# Phiips_212_r3.net
KiCad netlist of a schematic drawn in EAGLE
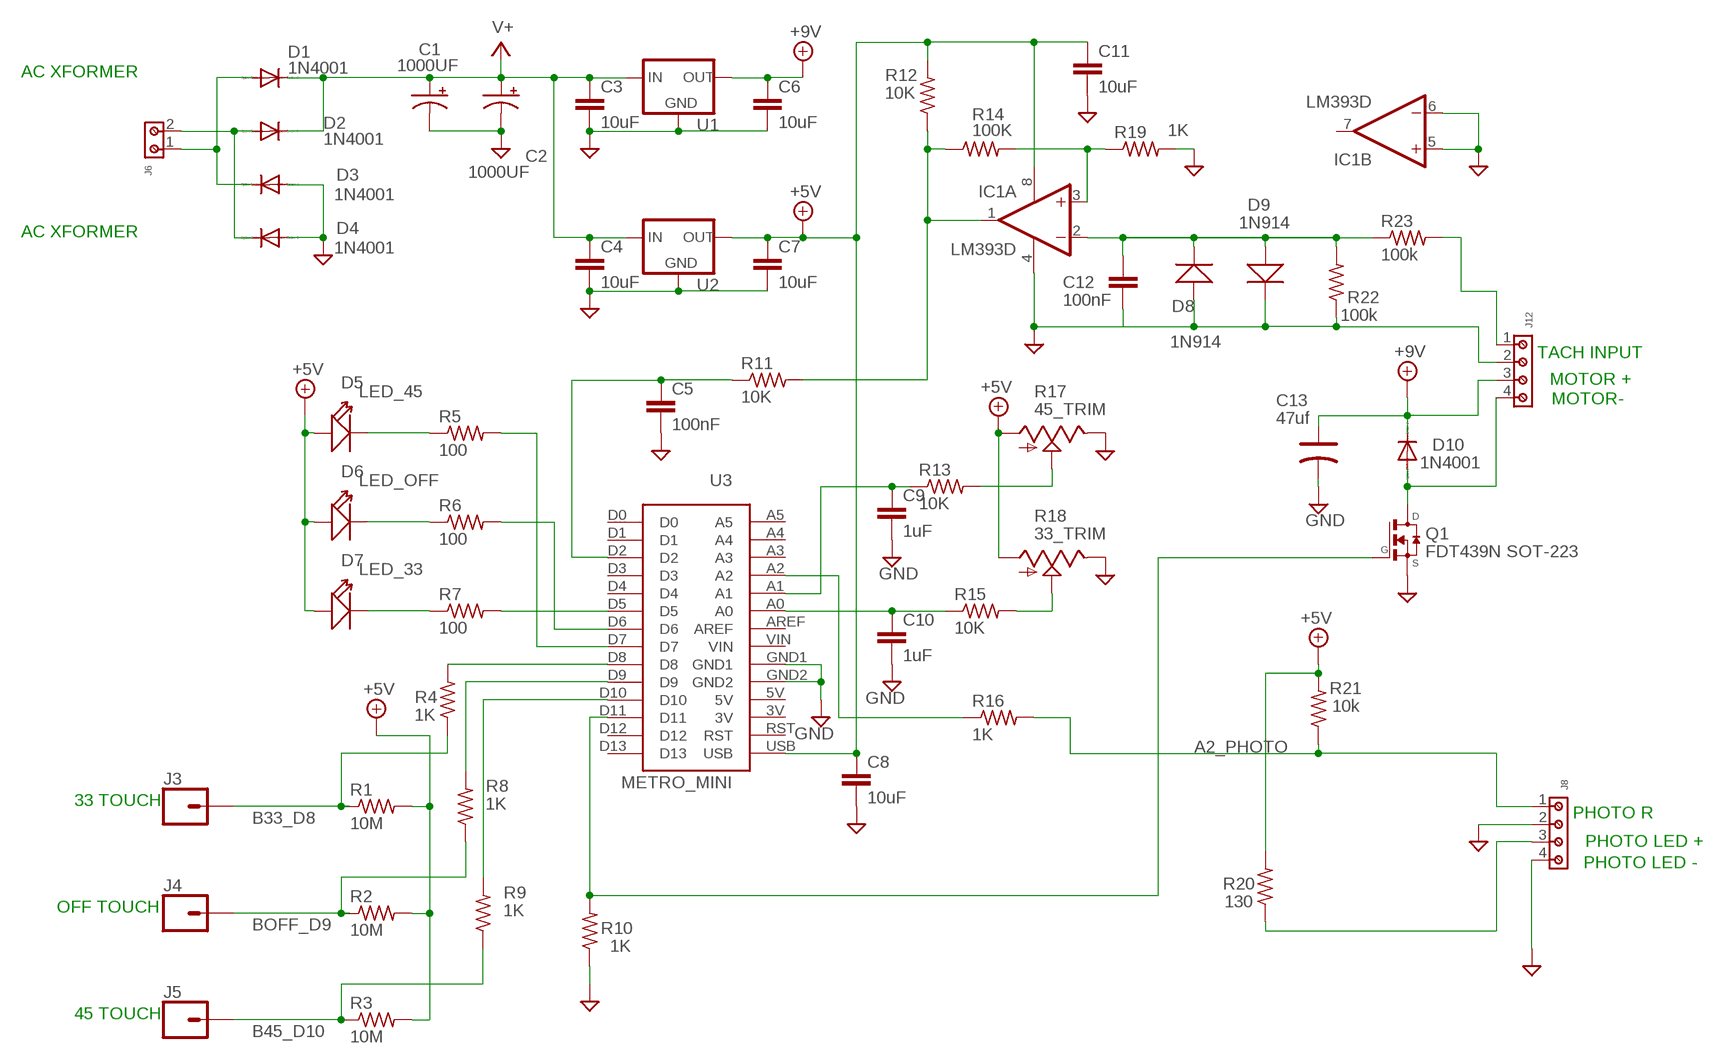
[diagram p0: schematic, sheet 1]

(export (version "E")
  (design (tool "Eeschema 10.0.6"))
  (components
    (comp (ref "C1")
      (value "1000UF")
      (footprint "eagle-import:CAPPAD1700W60L1040D500P")
      (libsource (lib "eagle-import") (part "1000UF"))
    )
    (comp (ref "C2")
      (value "1000UF")
      (footprint "eagle-import:CAPPAD1700W60L1040D500P")
      (libsource (lib "eagle-import") (part "1000UF"))
    )
    (comp (ref "C3")
      (value "10uF")
      (footprint "eagle-import:1206")
      (libsource (lib "eagle-import") (part "10UF-1206-6.3V-20%"))
    )
    (comp (ref "C4")
      (value "10uF")
      (footprint "eagle-import:1206")
      (libsource (lib "eagle-import") (part "10UF-1206-6.3V-20%"))
    )
    (comp (ref "C5")
      (value "100nF")
      (footprint "eagle-import:0805")
      (libsource (lib "eagle-import") (part "10UF-0805-10V-10%"))
    )
    (comp (ref "C6")
      (value "10uF")
      (footprint "eagle-import:1206")
      (libsource (lib "eagle-import") (part "10UF-1206-6.3V-20%"))
    )
    (comp (ref "C7")
      (value "10uF")
      (footprint "eagle-import:1206")
      (libsource (lib "eagle-import") (part "10UF-1206-6.3V-20%"))
    )
    (comp (ref "C8")
      (value "10uF")
      (footprint "eagle-import:1206")
      (libsource (lib "eagle-import") (part "10UF-1206-6.3V-20%"))
    )
    (comp (ref "C9")
      (value "1uF")
      (footprint "eagle-import:1206")
      (libsource (lib "eagle-import") (part "10UF-1206-6.3V-20%"))
    )
    (comp (ref "C10")
      (value "1uF")
      (footprint "eagle-import:1206")
      (libsource (lib "eagle-import") (part "10UF-1206-6.3V-20%"))
    )
    (comp (ref "C11")
      (value "10uF")
      (footprint "eagle-import:1206")
      (libsource (lib "eagle-import") (part "10UF-1206-6.3V-20%"))
    )
    (comp (ref "C12")
      (value "100nF")
      (footprint "eagle-import:0805")
      (libsource (lib "eagle-import") (part "10UF-0805-10V-10%"))
    )
    (comp (ref "C13")
      (value "47uf")
      (footprint "eagle-import:AVX-D")
      (fields (field (name "MPN") "TAJD477*006#NJ"))
      (libsource (lib "eagle-import") (part "TANTALUM-SMD-470UF-6.3V(AVX-D)"))
    )
    (comp (ref "D1")
      (value "1N4001")
      (footprint "eagle-import:DO41-10")
      (libsource (lib "eagle-import") (part "1N4004"))
    )
    (comp (ref "D2")
      (value "1N4001")
      (footprint "eagle-import:DO41-10")
      (libsource (lib "eagle-import") (part "1N4004"))
    )
    (comp (ref "D3")
      (value "1N4001")
      (footprint "eagle-import:DO41-10")
      (libsource (lib "eagle-import") (part "1N4004"))
    )
    (comp (ref "D4")
      (value "1N4001")
      (footprint "eagle-import:DO41-10")
      (libsource (lib "eagle-import") (part "1N4004"))
    )
    (comp (ref "D5")
      (value "LED_45")
      (footprint "eagle-import:LED2-2.54-D5.0MM")
      (fields (field (name "MPN") "504WC"))
      (libsource (lib "eagle-import") (part "DIP-LED-TRANSPARENT-WHITE(2P-D5MM)"))
    )
    (comp (ref "D6")
      (value "LED_OFF")
      (footprint "eagle-import:LED2-2.54-D5.0MM")
      (fields (field (name "MPN") "504WC"))
      (libsource (lib "eagle-import") (part "DIP-LED-TRANSPARENT-WHITE(2P-D5MM)"))
    )
    (comp (ref "D7")
      (value "LED_33")
      (footprint "eagle-import:LED2-2.54-D5.0MM")
      (fields (field (name "MPN") "504WC"))
      (libsource (lib "eagle-import") (part "DIP-LED-TRANSPARENT-WHITE(2P-D5MM)"))
    )
    (comp (ref "D8")
      (value "1N914")
      (footprint "eagle-import:DO-41")
      (fields (field (name "MPN") "1N4004"))
      (libsource (lib "eagle-import") (part "DIP-DIODE-400V-1A(DO-41)"))
    )
    (comp (ref "D9")
      (value "1N914")
      (footprint "eagle-import:DO-41")
      (fields (field (name "MPN") "1N4004"))
      (libsource (lib "eagle-import") (part "DIP-DIODE-400V-1A(DO-41)"))
    )
    (comp (ref "D10")
      (value "1N4001")
      (footprint "eagle-import:DO41-10")
      (libsource (lib "eagle-import") (part "1N4004"))
    )
    (comp (ref "IC1")
      (value "LM393D")
      (footprint "eagle-import:SO08")
      (libsource (lib "eagle-import") (part "LM393D"))
    )
    (comp (ref "J3")
      (value "CONN_01OFFSET")
      (footprint "eagle-import:1X01_OFFSET")
      (libsource (lib "eagle-import") (part "CONN_01OFFSET"))
    )
    (comp (ref "J4")
      (value "CONN_01OFFSET")
      (footprint "eagle-import:1X01_OFFSET")
      (libsource (lib "eagle-import") (part "CONN_01OFFSET"))
    )
    (comp (ref "J5")
      (value "CONN_01OFFSET")
      (footprint "eagle-import:1X01_OFFSET")
      (libsource (lib "eagle-import") (part "CONN_01OFFSET"))
    )
    (comp (ref "J6")
      (value "691131710002")
      (footprint "eagle-import:691131710002")
      (libsource (lib "eagle-import") (part "691131710002"))
    )
    (comp (ref "J8")
      (value "691131710004")
      (footprint "eagle-import:691131710004")
      (libsource (lib "eagle-import") (part "691131710004"))
    )
    (comp (ref "J12")
      (value "691131710004")
      (footprint "eagle-import:691131710004")
      (libsource (lib "eagle-import") (part "691131710004"))
    )
    (comp (ref "Q1")
      (value "FDT439N SOT-223")
      (footprint "eagle-import:SOT-223")
      (libsource (lib "eagle-import") (part "FDT439NSOT-223"))
    )
    (comp (ref "R1")
      (value "10M")
      (footprint "eagle-import:M1206")
      (libsource (lib "eagle-import") (part "R-US_M1206"))
    )
    (comp (ref "R2")
      (value "10M")
      (footprint "eagle-import:M1206")
      (libsource (lib "eagle-import") (part "R-US_M1206"))
    )
    (comp (ref "R3")
      (value "10M")
      (footprint "eagle-import:M1206")
      (libsource (lib "eagle-import") (part "R-US_M1206"))
    )
    (comp (ref "R4")
      (value "1K")
      (footprint "eagle-import:M1206")
      (libsource (lib "eagle-import") (part "R-US_M1206"))
    )
    (comp (ref "R5")
      (value "100")
      (footprint "eagle-import:M1206")
      (libsource (lib "eagle-import") (part "R-US_M1206"))
    )
    (comp (ref "R6")
      (value "100")
      (footprint "eagle-import:M1206")
      (libsource (lib "eagle-import") (part "R-US_M1206"))
    )
    (comp (ref "R7")
      (value "100")
      (footprint "eagle-import:M1206")
      (libsource (lib "eagle-import") (part "R-US_M1206"))
    )
    (comp (ref "R8")
      (value "1K")
      (footprint "eagle-import:M1206")
      (libsource (lib "eagle-import") (part "R-US_M1206"))
    )
    (comp (ref "R9")
      (value "1K")
      (footprint "eagle-import:M1206")
      (libsource (lib "eagle-import") (part "R-US_M1206"))
    )
    (comp (ref "R10")
      (value "1K")
      (footprint "eagle-import:M1206")
      (libsource (lib "eagle-import") (part "R-US_M1206"))
    )
    (comp (ref "R11")
      (value "10K")
      (footprint "eagle-import:M1206")
      (libsource (lib "eagle-import") (part "R-US_M1206"))
    )
    (comp (ref "R12")
      (value "10K")
      (footprint "eagle-import:M1206")
      (libsource (lib "eagle-import") (part "R-US_M1206"))
    )
    (comp (ref "R13")
      (value "10K")
      (footprint "eagle-import:M1206")
      (libsource (lib "eagle-import") (part "R-US_M1206"))
    )
    (comp (ref "R14")
      (value "100K")
      (footprint "eagle-import:M1206")
      (libsource (lib "eagle-import") (part "R-US_M1206"))
    )
    (comp (ref "R15")
      (value "10K")
      (footprint "eagle-import:M1206")
      (libsource (lib "eagle-import") (part "R-US_M1206"))
    )
    (comp (ref "R16")
      (value "1K")
      (footprint "eagle-import:M1206")
      (libsource (lib "eagle-import") (part "R-US_M1206"))
    )
    (comp (ref "R17")
      (value "45_TRIM")
      (footprint "eagle-import:PH212_POT")
      (libsource (lib "eagle-import") (part "POTS212_POT"))
    )
    (comp (ref "R18")
      (value "33_TRIM")
      (footprint "eagle-import:PH212_POT")
      (libsource (lib "eagle-import") (part "POTS212_POT"))
    )
    (comp (ref "R19")
      (value "1K")
      (footprint "eagle-import:M1206")
      (libsource (lib "eagle-import") (part "R-US_M1206"))
    )
    (comp (ref "R20")
      (value "130")
      (footprint "eagle-import:M1206")
      (libsource (lib "eagle-import") (part "R-US_M1206"))
    )
    (comp (ref "R21")
      (value "10k")
      (footprint "eagle-import:M1206")
      (libsource (lib "eagle-import") (part "R-US_M1206"))
    )
    (comp (ref "R22")
      (value "100k")
      (footprint "eagle-import:M1206")
      (libsource (lib "eagle-import") (part "R-US_M1206"))
    )
    (comp (ref "R23")
      (value "100k")
      (footprint "eagle-import:M1206")
      (libsource (lib "eagle-import") (part "R-US_M1206"))
    )
    (comp (ref "U1")
      (value "V_REG_78XXSIDE")
      (footprint "eagle-import:78XXL")
      (libsource (lib "eagle-import") (part "V_REG_78XXSIDE"))
    )
    (comp (ref "U2")
      (value "V_REG_78XXSIDE")
      (footprint "eagle-import:78XXL")
      (libsource (lib "eagle-import") (part "V_REG_78XXSIDE"))
    )
    (comp (ref "U3")
      (value "METRO_MINI")
      (footprint "eagle-import:METRO_MINI")
      (libsource (lib "eagle-import") (part "METRO_MINI"))
    )
  )
  (nets
    (net (code "1") (name "+5V") (class "Default")
      (node (ref "C11") (pin "1") (pinfunction "1_1") (pintype "passive"))
      (node (ref "C7") (pin "1") (pinfunction "1_1") (pintype "passive"))
      (node (ref "C8") (pin "1") (pinfunction "1_1") (pintype "passive"))
      (node (ref "D5") (pin "+") (pinfunction "+_+") (pintype "passive"))
      (node (ref "D6") (pin "+") (pinfunction "+_+") (pintype "passive"))
      (node (ref "D7") (pin "+") (pinfunction "+_+") (pintype "passive"))
      (node (ref "IC1") (pin "8") (pinfunction "V+_8") (pintype "power_in"))
      (node (ref "R1") (pin "2") (pinfunction "2_2") (pintype "passive"))
      (node (ref "R12") (pin "2") (pinfunction "2_2") (pintype "passive"))
      (node (ref "R17") (pin "1") (pinfunction "A_1") (pintype "passive"))
      (node (ref "R18") (pin "1") (pinfunction "A_1") (pintype "passive"))
      (node (ref "R2") (pin "2") (pinfunction "2_2") (pintype "passive"))
      (node (ref "R20") (pin "2") (pinfunction "2_2") (pintype "passive"))
      (node (ref "R21") (pin "2") (pinfunction "2_2") (pintype "passive"))
      (node (ref "R3") (pin "2") (pinfunction "2_2") (pintype "passive"))
      (node (ref "U2") (pin "OUT") (pinfunction "OUT_OUT") (pintype "passive"))
      (node (ref "U3") (pin "USB") (pinfunction "USB_USB") (pintype "power_in"))
    )
    (net (code "2") (name "+9V") (class "Default")
      (node (ref "C13") (pin "+") (pinfunction "+_+") (pintype "passive"))
      (node (ref "C6") (pin "1") (pinfunction "1_1") (pintype "passive"))
      (node (ref "D10") (pin "C") (pinfunction "C_C") (pintype "passive"))
      (node (ref "J12") (pin "3") (pinfunction "3_3") (pintype "passive"))
      (node (ref "U1") (pin "OUT") (pinfunction "OUT_OUT") (pintype "passive"))
    )
    (net (code "3") (name "/A2_PHOTO") (class "Default")
      (node (ref "J8") (pin "1") (pinfunction "1_1") (pintype "passive"))
      (node (ref "R16") (pin "2") (pinfunction "2_2") (pintype "passive"))
      (node (ref "R21") (pin "1") (pinfunction "1_1") (pintype "passive"))
    )
    (net (code "4") (name "/B33_D8") (class "Default")
      (node (ref "J3") (pin "1") (pinfunction "1_1") (pintype "passive"))
      (node (ref "R1") (pin "1") (pinfunction "1_1") (pintype "passive"))
      (node (ref "R4") (pin "1") (pinfunction "1_1") (pintype "passive"))
    )
    (net (code "5") (name "/B45_D10") (class "Default")
      (node (ref "J5") (pin "1") (pinfunction "1_1") (pintype "passive"))
      (node (ref "R3") (pin "1") (pinfunction "1_1") (pintype "passive"))
      (node (ref "R9") (pin "1") (pinfunction "1_1") (pintype "passive"))
    )
    (net (code "6") (name "/BOFF_D9") (class "Default")
      (node (ref "J4") (pin "1") (pinfunction "1_1") (pintype "passive"))
      (node (ref "R2") (pin "1") (pinfunction "1_1") (pintype "passive"))
      (node (ref "R8") (pin "1") (pinfunction "1_1") (pintype "passive"))
    )
    (net (code "7") (name "GND") (class "Default")
      (node (ref "C1") (pin "2") (pinfunction "-_2") (pintype "passive"))
      (node (ref "C10") (pin "2") (pinfunction "2_2") (pintype "passive"))
      (node (ref "C11") (pin "2") (pinfunction "2_2") (pintype "passive"))
      (node (ref "C12") (pin "2") (pinfunction "2_2") (pintype "passive"))
      (node (ref "C13") (pin "-") (pinfunction "-_-") (pintype "passive"))
      (node (ref "C2") (pin "2") (pinfunction "-_2") (pintype "passive"))
      (node (ref "C3") (pin "2") (pinfunction "2_2") (pintype "passive"))
      (node (ref "C4") (pin "2") (pinfunction "2_2") (pintype "passive"))
      (node (ref "C5") (pin "2") (pinfunction "2_2") (pintype "passive"))
      (node (ref "C6") (pin "2") (pinfunction "2_2") (pintype "passive"))
      (node (ref "C7") (pin "2") (pinfunction "2_2") (pintype "passive"))
      (node (ref "C8") (pin "2") (pinfunction "2_2") (pintype "passive"))
      (node (ref "C9") (pin "2") (pinfunction "2_2") (pintype "passive"))
      (node (ref "D3") (pin "A") (pinfunction "A_A") (pintype "passive"))
      (node (ref "D4") (pin "A") (pinfunction "A_A") (pintype "passive"))
      (node (ref "D8") (pin "1") (pinfunction "+_1") (pintype "passive"))
      (node (ref "D9") (pin "2") (pinfunction "-_2") (pintype "passive"))
      (node (ref "IC1") (pin "4") (pinfunction "V-_4") (pintype "power_in"))
      (node (ref "IC1") (pin "5") (pinfunction "+IN_5") (pintype "input"))
      (node (ref "IC1") (pin "6") (pinfunction "-IN_6") (pintype "input"))
      (node (ref "J12") (pin "2") (pinfunction "2_2") (pintype "passive"))
      (node (ref "J8") (pin "2") (pinfunction "2_2") (pintype "passive"))
      (node (ref "J8") (pin "4") (pinfunction "4_4") (pintype "passive"))
      (node (ref "Q1") (pin "3") (pinfunction "S_3") (pintype "passive"))
      (node (ref "R10") (pin "1") (pinfunction "1_1") (pintype "passive"))
      (node (ref "R17") (pin "3") (pinfunction "E_3") (pintype "passive"))
      (node (ref "R18") (pin "3") (pinfunction "E_3") (pintype "passive"))
      (node (ref "R19") (pin "2") (pinfunction "2_2") (pintype "passive"))
      (node (ref "R22") (pin "1") (pinfunction "1_1") (pintype "passive"))
      (node (ref "U1") (pin "GND") (pinfunction "GND_GND") (pintype "input"))
      (node (ref "U2") (pin "GND") (pinfunction "GND_GND") (pintype "input"))
      (node (ref "U3") (pin "GND1") (pinfunction "GND1_GND1") (pintype "power_in"))
      (node (ref "U3") (pin "GND2") (pinfunction "GND2_GND2") (pintype "power_in"))
    )
    (net (code "8") (name "Net-(C5-Pad1)") (class "Default")
      (node (ref "C5") (pin "1") (pinfunction "1_1") (pintype "passive"))
      (node (ref "R11") (pin "1") (pinfunction "1_1") (pintype "passive"))
      (node (ref "U3") (pin "D2") (pinfunction "D2_D2") (pintype "bidirectional"))
    )
    (net (code "9") (name "Net-(C9-Pad1)") (class "Default")
      (node (ref "C9") (pin "1") (pinfunction "1_1") (pintype "passive"))
      (node (ref "R13") (pin "1") (pinfunction "1_1") (pintype "passive"))
      (node (ref "U3") (pin "A1") (pinfunction "A1_A1") (pintype "bidirectional"))
    )
    (net (code "10") (name "Net-(C10-Pad1)") (class "Default")
      (node (ref "C10") (pin "1") (pinfunction "1_1") (pintype "passive"))
      (node (ref "R15") (pin "1") (pinfunction "1_1") (pintype "passive"))
      (node (ref "U3") (pin "A0") (pinfunction "A0_A0") (pintype "bidirectional"))
    )
    (net (code "11") (name "Net-(D1-PadA)") (class "Default")
      (node (ref "D1") (pin "A") (pinfunction "A_A") (pintype "passive"))
      (node (ref "D3") (pin "C") (pinfunction "C_C") (pintype "passive"))
      (node (ref "J6") (pin "1") (pinfunction "1_1") (pintype "passive"))
    )
    (net (code "12") (name "Net-(D2-PadA)") (class "Default")
      (node (ref "D2") (pin "A") (pinfunction "A_A") (pintype "passive"))
      (node (ref "D4") (pin "C") (pinfunction "C_C") (pintype "passive"))
      (node (ref "J6") (pin "2") (pinfunction "2_2") (pintype "passive"))
    )
    (net (code "13") (name "Net-(D5-Pad-)") (class "Default")
      (node (ref "D5") (pin "-") (pinfunction "-_-") (pintype "passive"))
      (node (ref "R5") (pin "1") (pinfunction "1_1") (pintype "passive"))
    )
    (net (code "14") (name "Net-(D6-Pad-)") (class "Default")
      (node (ref "D6") (pin "-") (pinfunction "-_-") (pintype "passive"))
      (node (ref "R6") (pin "1") (pinfunction "1_1") (pintype "passive"))
    )
    (net (code "15") (name "Net-(D7-Pad-)") (class "Default")
      (node (ref "D7") (pin "-") (pinfunction "-_-") (pintype "passive"))
      (node (ref "R7") (pin "1") (pinfunction "1_1") (pintype "passive"))
    )
    (net (code "16") (name "Net-(D8--)") (class "Default")
      (node (ref "C12") (pin "1") (pinfunction "1_1") (pintype "passive"))
      (node (ref "D8") (pin "2") (pinfunction "-_2") (pintype "passive"))
      (node (ref "D9") (pin "1") (pinfunction "+_1") (pintype "passive"))
      (node (ref "IC1") (pin "2") (pinfunction "-IN_2") (pintype "input"))
      (node (ref "R22") (pin "2") (pinfunction "2_2") (pintype "passive"))
      (node (ref "R23") (pin "1") (pinfunction "1_1") (pintype "passive"))
    )
    (net (code "17") (name "Net-(D10-PadA)") (class "Default")
      (node (ref "D10") (pin "A") (pinfunction "A_A") (pintype "passive"))
      (node (ref "J12") (pin "4") (pinfunction "4_4") (pintype "passive"))
      (node (ref "Q1") (pin "2") (pinfunction "D_2") (pintype "passive"))
      (node (ref "Q1") (pin "4") (pinfunction "D_4") (pintype "passive"))
    )
    (net (code "18") (name "Net-(IC1A-+IN)") (class "Default")
      (node (ref "IC1") (pin "3") (pinfunction "+IN_3") (pintype "input"))
      (node (ref "R14") (pin "2") (pinfunction "2_2") (pintype "passive"))
      (node (ref "R19") (pin "1") (pinfunction "1_1") (pintype "passive"))
    )
    (net (code "19") (name "Net-(IC1A-OUT)") (class "Default")
      (node (ref "IC1") (pin "1") (pinfunction "OUT_1") (pintype "output"))
      (node (ref "R11") (pin "2") (pinfunction "2_2") (pintype "passive"))
      (node (ref "R12") (pin "1") (pinfunction "1_1") (pintype "passive"))
      (node (ref "R14") (pin "1") (pinfunction "1_1") (pintype "passive"))
    )
    (net (code "20") (name "Net-(J8-Pad3)") (class "Default")
      (node (ref "J8") (pin "3") (pinfunction "3_3") (pintype "passive"))
      (node (ref "R20") (pin "1") (pinfunction "1_1") (pintype "passive"))
    )
    (net (code "21") (name "Net-(J12-Pad1)") (class "Default")
      (node (ref "J12") (pin "1") (pinfunction "1_1") (pintype "passive"))
      (node (ref "R23") (pin "2") (pinfunction "2_2") (pintype "passive"))
    )
    (net (code "22") (name "Net-(Q1-G)") (class "Default")
      (node (ref "Q1") (pin "1") (pinfunction "G_1") (pintype "passive"))
      (node (ref "R10") (pin "2") (pinfunction "2_2") (pintype "passive"))
      (node (ref "U3") (pin "D11") (pinfunction "D11_D11") (pintype "bidirectional"))
    )
    (net (code "23") (name "Net-(R4-Pad2)") (class "Default")
      (node (ref "R4") (pin "2") (pinfunction "2_2") (pintype "passive"))
      (node (ref "U3") (pin "D8") (pinfunction "D8_D8") (pintype "bidirectional"))
    )
    (net (code "24") (name "Net-(R5-Pad2)") (class "Default")
      (node (ref "R5") (pin "2") (pinfunction "2_2") (pintype "passive"))
      (node (ref "U3") (pin "D7") (pinfunction "D7_D7") (pintype "bidirectional"))
    )
    (net (code "25") (name "Net-(R6-Pad2)") (class "Default")
      (node (ref "R6") (pin "2") (pinfunction "2_2") (pintype "passive"))
      (node (ref "U3") (pin "D6") (pinfunction "D6_D6") (pintype "bidirectional"))
    )
    (net (code "26") (name "Net-(R7-Pad2)") (class "Default")
      (node (ref "R7") (pin "2") (pinfunction "2_2") (pintype "passive"))
      (node (ref "U3") (pin "D5") (pinfunction "D5_D5") (pintype "bidirectional"))
    )
    (net (code "27") (name "Net-(R8-Pad2)") (class "Default")
      (node (ref "R8") (pin "2") (pinfunction "2_2") (pintype "passive"))
      (node (ref "U3") (pin "D9") (pinfunction "D9_D9") (pintype "bidirectional"))
    )
    (net (code "28") (name "Net-(R9-Pad2)") (class "Default")
      (node (ref "R9") (pin "2") (pinfunction "2_2") (pintype "passive"))
      (node (ref "U3") (pin "D10") (pinfunction "D10_D10") (pintype "bidirectional"))
    )
    (net (code "29") (name "Net-(R16-Pad1)") (class "Default")
      (node (ref "R16") (pin "1") (pinfunction "1_1") (pintype "passive"))
      (node (ref "U3") (pin "A2") (pinfunction "A2_A2") (pintype "bidirectional"))
    )
    (net (code "30") (name "Net-(R17-S)") (class "Default")
      (node (ref "R13") (pin "2") (pinfunction "2_2") (pintype "passive"))
      (node (ref "R17") (pin "2") (pinfunction "S_2") (pintype "passive"))
    )
    (net (code "31") (name "Net-(R18-S)") (class "Default")
      (node (ref "R15") (pin "2") (pinfunction "2_2") (pintype "passive"))
      (node (ref "R18") (pin "2") (pinfunction "S_2") (pintype "passive"))
    )
    (net (code "32") (name "V+") (class "Default")
      (node (ref "C1") (pin "1") (pinfunction "+_1") (pintype "passive"))
      (node (ref "C2") (pin "1") (pinfunction "+_1") (pintype "passive"))
      (node (ref "C3") (pin "1") (pinfunction "1_1") (pintype "passive"))
      (node (ref "C4") (pin "1") (pinfunction "1_1") (pintype "passive"))
      (node (ref "D1") (pin "C") (pinfunction "C_C") (pintype "passive"))
      (node (ref "D2") (pin "C") (pinfunction "C_C") (pintype "passive"))
      (node (ref "U1") (pin "IN") (pinfunction "IN_IN") (pintype "input"))
      (node (ref "U2") (pin "IN") (pinfunction "IN_IN") (pintype "input"))
    )
    (net (code "33") (name "unconnected-(IC1B-OUT-Pad7)") (class "Default")
      (node (ref "IC1") (pin "7") (pinfunction "OUT_7") (pintype "output"))
    )
    (net (code "34") (name "unconnected-(U3-Pad3V)") (class "Default")
      (node (ref "U3") (pin "3V") (pinfunction "3V_3V") (pintype "bidirectional"))
    )
    (net (code "35") (name "unconnected-(U3-Pad5V)") (class "Default")
      (node (ref "U3") (pin "5V") (pinfunction "5V_5V") (pintype "bidirectional"))
    )
    (net (code "36") (name "unconnected-(U3-PadA3)") (class "Default")
      (node (ref "U3") (pin "A3") (pinfunction "A3_A3") (pintype "bidirectional"))
    )
    (net (code "37") (name "unconnected-(U3-PadA4)") (class "Default")
      (node (ref "U3") (pin "A4") (pinfunction "A4_A4") (pintype "bidirectional"))
    )
    (net (code "38") (name "unconnected-(U3-PadA5)") (class "Default")
      (node (ref "U3") (pin "A5") (pinfunction "A5_A5") (pintype "bidirectional"))
    )
    (net (code "39") (name "unconnected-(U3-PadAREF)") (class "Default")
      (node (ref "U3") (pin "AREF") (pinfunction "AREF_AREF") (pintype "bidirectional"))
    )
    (net (code "40") (name "unconnected-(U3-PadD0)") (class "Default")
      (node (ref "U3") (pin "D0") (pinfunction "D0_D0") (pintype "bidirectional"))
    )
    (net (code "41") (name "unconnected-(U3-PadD1)") (class "Default")
      (node (ref "U3") (pin "D1") (pinfunction "D1_D1") (pintype "bidirectional"))
    )
    (net (code "42") (name "unconnected-(U3-PadD3)") (class "Default")
      (node (ref "U3") (pin "D3") (pinfunction "D3_D3") (pintype "bidirectional"))
    )
    (net (code "43") (name "unconnected-(U3-PadD4)") (class "Default")
      (node (ref "U3") (pin "D4") (pinfunction "D4_D4") (pintype "bidirectional"))
    )
    (net (code "44") (name "unconnected-(U3-PadD12)") (class "Default")
      (node (ref "U3") (pin "D12") (pinfunction "D12_D12") (pintype "bidirectional"))
    )
    (net (code "45") (name "unconnected-(U3-PadD13)") (class "Default")
      (node (ref "U3") (pin "D13") (pinfunction "D13_D13") (pintype "bidirectional"))
    )
    (net (code "46") (name "unconnected-(U3-PadRST)") (class "Default")
      (node (ref "U3") (pin "RST") (pinfunction "RST_RST") (pintype "bidirectional"))
    )
    (net (code "47") (name "unconnected-(U3-PadVIN)") (class "Default")
      (node (ref "U3") (pin "VIN") (pinfunction "VIN_VIN") (pintype "bidirectional"))
    )
  )
)
